# Core_CNC_shield.net
KiCad netlist of a schematic drawn in Altium Designer
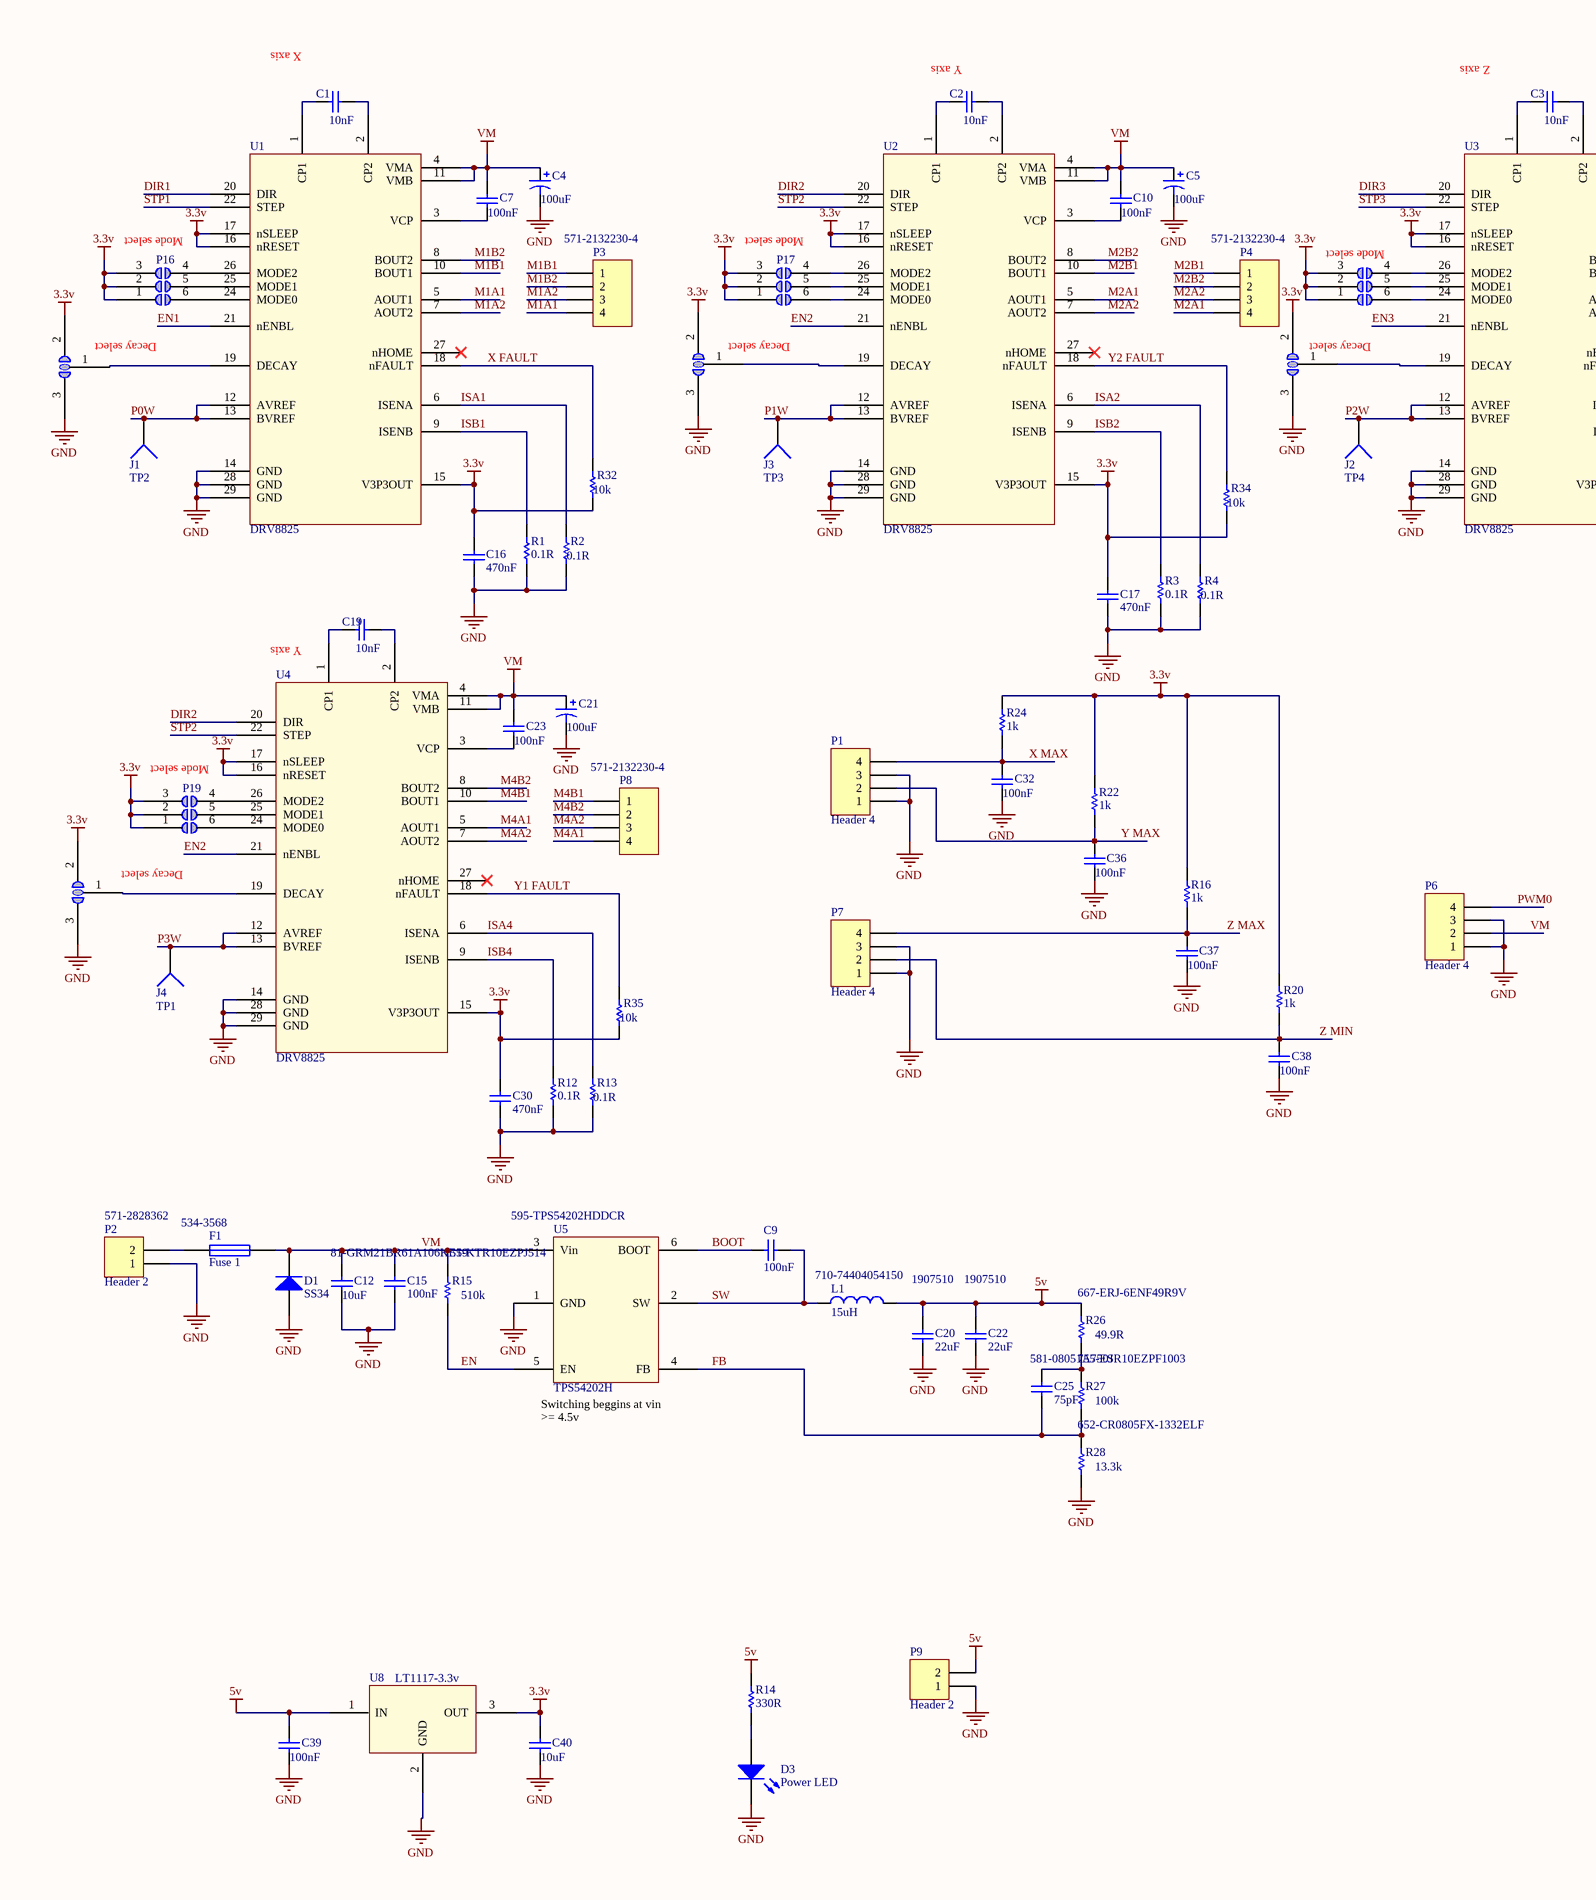
[diagram p0: Core CNC shield.SchDoc, left]
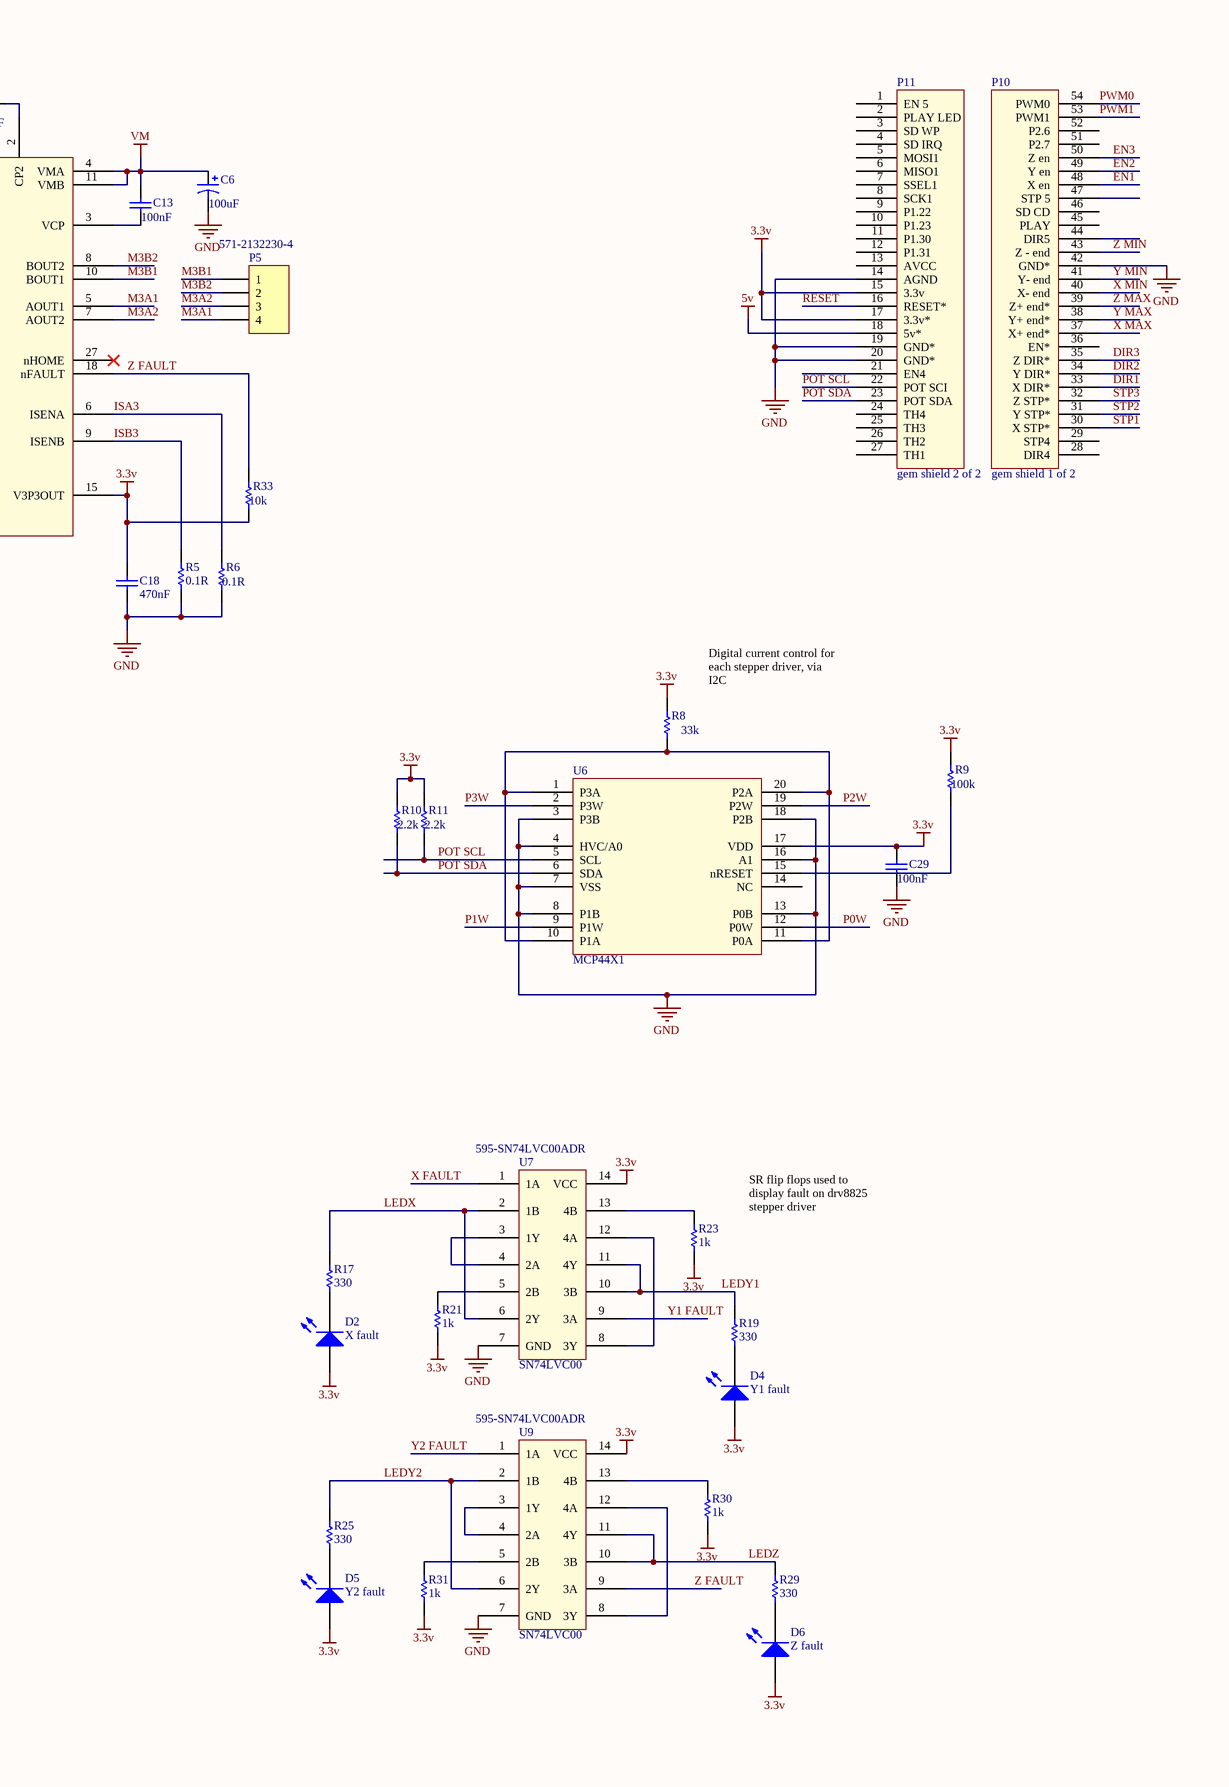
[diagram p1: Core CNC shield.SchDoc, right]

(export (version "E")
  (design (tool "Eeschema 10.0.6"))
  (components
    (comp (ref "C1")
      (value "10nF")
      (footprint "0805")
      (description "Capacitor")
      (fields (field (name "PUBLISHER") "Altium Limited"))
      (libsource (lib "Miscellaneous Devices") (part "Cap"))
    )
    (comp (ref "C2")
      (value "10nF")
      (footprint "0805")
      (description "Capacitor")
      (fields (field (name "PUBLISHER") "Altium Limited"))
      (libsource (lib "Miscellaneous Devices") (part "Cap"))
    )
    (comp (ref "C3")
      (value "10nF")
      (footprint "0805")
      (description "Capacitor")
      (fields (field (name "PUBLISHER") "Altium Limited"))
      (libsource (lib "Miscellaneous Devices") (part "Cap"))
    )
    (comp (ref "C4")
      (value "100uF")
      (footprint "470uf/ 100uf 50v smd")
      (description "Polarized Capacitor (Radial)")
      (fields (field (name "PUBLISHER") "Altium Limited"))
      (libsource (lib "Miscellaneous Devices") (part "Cap Pol1"))
    )
    (comp (ref "C5")
      (value "100uF")
      (footprint "470uf/ 100uf 50v smd")
      (description "Polarized Capacitor (Radial)")
      (fields (field (name "PUBLISHER") "Altium Limited"))
      (libsource (lib "Miscellaneous Devices") (part "Cap Pol1"))
    )
    (comp (ref "C6")
      (value "100uF")
      (footprint "470uf/ 100uf 50v smd")
      (description "Polarized Capacitor (Radial)")
      (fields (field (name "PUBLISHER") "Altium Limited"))
      (libsource (lib "Miscellaneous Devices") (part "Cap Pol1"))
    )
    (comp (ref "C7")
      (value "100nF")
      (footprint "0805")
      (description "Capacitor")
      (fields (field (name "PUBLISHER") "Altium Limited"))
      (libsource (lib "Miscellaneous Devices") (part "Cap"))
    )
    (comp (ref "C9")
      (value "100nF")
      (footprint "0805")
      (description "Capacitor")
      (fields (field (name "PUBLISHER") "Altium Limited"))
      (libsource (lib "Miscellaneous Devices") (part "Cap"))
    )
    (comp (ref "C10")
      (value "100nF")
      (footprint "0805")
      (description "Capacitor")
      (fields (field (name "PUBLISHER") "Altium Limited"))
      (libsource (lib "Miscellaneous Devices") (part "Cap"))
    )
    (comp (ref "C12")
      (value "10uF")
      (footprint "0805")
      (description "Capacitor")
      (fields
        (field (name "SUPPLIER PART NUMBER 1") "81-GRM21BR61A106KE19")
        (field (name "PUBLISHER") "Altium Limited")
      )
      (libsource (lib "Miscellaneous Devices") (part "Cap"))
    )
    (comp (ref "C13")
      (value "100nF")
      (footprint "0805")
      (description "Capacitor")
      (fields (field (name "PUBLISHER") "Altium Limited"))
      (libsource (lib "Miscellaneous Devices") (part "Cap"))
    )
    (comp (ref "C15")
      (value "100nF")
      (footprint "0805")
      (description "Capacitor")
      (fields (field (name "PUBLISHER") "Altium Limited"))
      (libsource (lib "Miscellaneous Devices") (part "Cap"))
    )
    (comp (ref "C16")
      (value "470nF")
      (footprint "0805")
      (description "Capacitor")
      (fields (field (name "PUBLISHER") "Altium Limited"))
      (libsource (lib "Miscellaneous Devices") (part "Cap"))
    )
    (comp (ref "C17")
      (value "470nF")
      (footprint "0805")
      (description "Capacitor")
      (fields (field (name "PUBLISHER") "Altium Limited"))
      (libsource (lib "Miscellaneous Devices") (part "Cap"))
    )
    (comp (ref "C18")
      (value "470nF")
      (footprint "0805")
      (description "Capacitor")
      (fields (field (name "PUBLISHER") "Altium Limited"))
      (libsource (lib "Miscellaneous Devices") (part "Cap"))
    )
    (comp (ref "C19")
      (value "10nF")
      (footprint "0805")
      (description "Capacitor")
      (fields (field (name "PUBLISHER") "Altium Limited"))
      (libsource (lib "Miscellaneous Devices") (part "Cap"))
    )
    (comp (ref "C20")
      (value "22uF")
      (footprint "0805")
      (description "Capacitor")
      (fields (field (name "SUPPLIER PART NUMBER 4") "1907510") (field (name "PUBLISHER") "Altium Limited"))
      (libsource (lib "Miscellaneous Devices") (part "Cap"))
    )
    (comp (ref "C21")
      (value "100uF")
      (footprint "470uf/ 100uf 50v smd")
      (description "Polarized Capacitor (Radial)")
      (fields (field (name "PUBLISHER") "Altium Limited"))
      (libsource (lib "Miscellaneous Devices") (part "Cap Pol1"))
    )
    (comp (ref "C22")
      (value "22uF")
      (footprint "0805")
      (description "Capacitor")
      (fields (field (name "SUPPLIER PART NUMBER 4") "1907510") (field (name "PUBLISHER") "Altium Limited"))
      (libsource (lib "Miscellaneous Devices") (part "Cap"))
    )
    (comp (ref "C23")
      (value "100nF")
      (footprint "0805")
      (description "Capacitor")
      (fields (field (name "PUBLISHER") "Altium Limited"))
      (libsource (lib "Miscellaneous Devices") (part "Cap"))
    )
    (comp (ref "C25")
      (value "75pF")
      (footprint "0805")
      (description "Capacitor")
      (fields
        (field (name "SUPPLIER PART NUMBER 1") "581-08051A750J")
        (field (name "PUBLISHER") "Altium Limited")
      )
      (libsource (lib "Miscellaneous Devices") (part "Cap"))
    )
    (comp (ref "C29")
      (value "100nF")
      (footprint "0805")
      (description "Capacitor")
      (fields (field (name "PUBLISHER") "Altium Limited"))
      (libsource (lib "Miscellaneous Devices") (part "Cap"))
    )
    (comp (ref "C30")
      (value "470nF")
      (footprint "0805")
      (description "Capacitor")
      (fields (field (name "PUBLISHER") "Altium Limited"))
      (libsource (lib "Miscellaneous Devices") (part "Cap"))
    )
    (comp (ref "C32")
      (value "100nF")
      (footprint "0805")
      (description "Capacitor")
      (fields (field (name "PUBLISHER") "Altium Limited"))
      (libsource (lib "Miscellaneous Devices") (part "Cap"))
    )
    (comp (ref "C36")
      (value "100nF")
      (footprint "0805")
      (description "Capacitor")
      (fields (field (name "PUBLISHER") "Altium Limited"))
      (libsource (lib "Miscellaneous Devices") (part "Cap"))
    )
    (comp (ref "C37")
      (value "100nF")
      (footprint "0805")
      (description "Capacitor")
      (fields (field (name "PUBLISHER") "Altium Limited"))
      (libsource (lib "Miscellaneous Devices") (part "Cap"))
    )
    (comp (ref "C38")
      (value "100nF")
      (footprint "0805")
      (description "Capacitor")
      (fields (field (name "PUBLISHER") "Altium Limited"))
      (libsource (lib "Miscellaneous Devices") (part "Cap"))
    )
    (comp (ref "C39")
      (value "100nF")
      (footprint "0805")
      (description "Capacitor")
      (fields (field (name "PUBLISHER") "Altium Limited"))
      (libsource (lib "Miscellaneous Devices") (part "Cap"))
    )
    (comp (ref "C40")
      (value "10uF")
      (footprint "0805")
      (description "Capacitor")
      (fields (field (name "PUBLISHER") "Altium Limited"))
      (libsource (lib "Miscellaneous Devices") (part "Cap"))
    )
    (comp (ref "D1")
      (value "SS34")
      (footprint "Diode")
      (description "Default Diode")
      (fields (field (name "PUBLISHER") "Altium Limited"))
      (libsource (lib "Miscellaneous Devices") (part "Diode"))
    )
    (comp (ref "D2")
      (value "X fault")
      (footprint "0805 LED")
      (description "Typical RED, GREEN, YELLOW, AMBER GaAs LED")
      (fields (field (name "PUBLISHER") "Altium Limited"))
      (libsource (lib "Miscellaneous Devices") (part "LED2"))
    )
    (comp (ref "D3")
      (value "Power LED")
      (footprint "0805 LED")
      (description "Typical RED, GREEN, YELLOW, AMBER GaAs LED")
      (fields (field (name "PUBLISHER") "Altium Limited"))
      (libsource (lib "Miscellaneous Devices") (part "LED2"))
    )
    (comp (ref "D4")
      (value "Y1 fault")
      (footprint "0805 LED")
      (description "Typical RED, GREEN, YELLOW, AMBER GaAs LED")
      (fields (field (name "PUBLISHER") "Altium Limited"))
      (libsource (lib "Miscellaneous Devices") (part "LED2"))
    )
    (comp (ref "D5")
      (value "Y2 fault")
      (footprint "0805 LED")
      (description "Typical RED, GREEN, YELLOW, AMBER GaAs LED")
      (fields (field (name "PUBLISHER") "Altium Limited"))
      (libsource (lib "Miscellaneous Devices") (part "LED2"))
    )
    (comp (ref "D6")
      (value "Z fault")
      (footprint "0805 LED")
      (description "Typical RED, GREEN, YELLOW, AMBER GaAs LED")
      (fields (field (name "PUBLISHER") "Altium Limited"))
      (libsource (lib "Miscellaneous Devices") (part "LED2"))
    )
    (comp (ref "F1")
      (value "Fuse 1")
      (footprint "mini auto fuse")
      (description "Fuse")
      (fields (field (name "SUPPLIER PART NUMBER 1") "534-3568") (field (name "PUBLISHER") "Altium Limited"))
      (libsource (lib "Miscellaneous Devices") (part "Fuse 1"))
    )
    (comp (ref "J1")
      (value "TP2")
      (footprint "test point")
      (description "Socket")
      (fields (field (name "PUBLISHER") "Altium Limited"))
      (libsource (lib "Miscellaneous Connectors") (part "Socket"))
    )
    (comp (ref "J2")
      (value "TP4")
      (footprint "test point")
      (description "Socket")
      (fields (field (name "PUBLISHER") "Altium Limited"))
      (libsource (lib "Miscellaneous Connectors") (part "Socket"))
    )
    (comp (ref "J3")
      (value "TP3")
      (footprint "test point")
      (description "Socket")
      (fields (field (name "PUBLISHER") "Altium Limited"))
      (libsource (lib "Miscellaneous Connectors") (part "Socket"))
    )
    (comp (ref "J4")
      (value "TP1")
      (footprint "test point")
      (description "Socket")
      (fields (field (name "PUBLISHER") "Altium Limited"))
      (libsource (lib "Miscellaneous Connectors") (part "Socket"))
    )
    (comp (ref "L1")
      (value "15uH")
      (footprint "SRN4018 inductor")
      (description "Inductor")
      (fields
        (field (name "SUPPLIER PART NUMBER 1") "710-74404054150")
        (field (name "Comment") "15uh")
        (field (name "PUBLISHER") "Altium Limited")
      )
      (libsource (lib "Miscellaneous Devices") (part "Inductor"))
    )
    (comp (ref "P1")
      (value "Header 4")
      (footprint "4 way screw")
      (description "Header, 4-Pin")
      (fields (field (name "PUBLISHER") "Altium Limited"))
      (libsource (lib "") (part "Header 4_1"))
    )
    (comp (ref "P2")
      (value "Header 2")
      (footprint "2 pin screw con")
      (description "Header, 2-Pin")
      (fields
        (field (name "SUPPLIER PART NUMBER 1") "571-2828362")
        (field (name "PUBLISHER") "Altium Limited")
      )
      (libsource (lib "Miscellaneous Connectors") (part "Header 2"))
    )
    (comp (ref "P3")
      (value "Header 4")
      (footprint "4 pin screw")
      (description "Header, 4-Pin")
      (fields
        (field (name "SUPPLIER PART NUMBER 1") "571-2132230-4")
        (field (name "PUBLISHER") "Altium Limited")
      )
      (libsource (lib "Miscellaneous Connectors") (part "Header 4"))
    )
    (comp (ref "P4")
      (value "Header 4")
      (footprint "4 pin screw")
      (description "Header, 4-Pin")
      (fields
        (field (name "SUPPLIER PART NUMBER 1") "571-2132230-4")
        (field (name "PUBLISHER") "Altium Limited")
      )
      (libsource (lib "Miscellaneous Connectors") (part "Header 4"))
    )
    (comp (ref "P5")
      (value "Header 4")
      (footprint "4 pin screw")
      (description "Header, 4-Pin")
      (fields
        (field (name "SUPPLIER PART NUMBER 1") "571-2132230-4")
        (field (name "PUBLISHER") "Altium Limited")
      )
      (libsource (lib "Miscellaneous Connectors") (part "Header 4"))
    )
    (comp (ref "P6")
      (value "Header 4")
      (footprint "4 way screw")
      (description "Header, 4-Pin")
      (fields (field (name "PUBLISHER") "Altium Limited"))
      (libsource (lib "") (part "Header 4_1"))
    )
    (comp (ref "P7")
      (value "Header 4")
      (footprint "4 way screw")
      (description "Header, 4-Pin")
      (fields (field (name "PUBLISHER") "Altium Limited"))
      (libsource (lib "") (part "Header 4_1"))
    )
    (comp (ref "P8")
      (value "Header 4")
      (footprint "4 pin screw")
      (description "Header, 4-Pin")
      (fields
        (field (name "SUPPLIER PART NUMBER 1") "571-2132230-4")
        (field (name "PUBLISHER") "Altium Limited")
      )
      (libsource (lib "Miscellaneous Connectors") (part "Header 4"))
    )
    (comp (ref "P9")
      (value "Header 2")
      (footprint "HDR1X2")
      (description "Header, 2-Pin")
      (fields (field (name "PUBLISHER") "Altium Limited"))
      (libsource (lib "Miscellaneous Connectors") (part "Header 2"))
    )
    (comp (ref "P10")
      (value "gem shield 1 of 2")
      (footprint "gem shield 1 of 2")
      (libsource (lib "32 bit cnc") (part "gem shield 1 of 2"))
    )
    (comp (ref "P11")
      (value "gem shield 2 of 2")
      (footprint "gem shield 2 of 2")
      (libsource (lib "32 bit cnc") (part "gem shield 2 of 2"))
    )
    (comp (ref "P14")
      (value "~")
      (footprint "2 way jumper")
      (libsource (lib "32 bit cnc") (part "voltage selector"))
    )
    (comp (ref "P15")
      (value "~")
      (footprint "2 way jumper")
      (libsource (lib "32 bit cnc") (part "voltage selector"))
    )
    (comp (ref "P16")
      (value "~")
      (footprint "3 way jumper")
      (libsource (lib "32 bit cnc") (part "3 way jumper"))
    )
    (comp (ref "P17")
      (value "~")
      (footprint "3 way jumper")
      (libsource (lib "32 bit cnc") (part "3 way jumper"))
    )
    (comp (ref "P18")
      (value "~")
      (footprint "3 way jumper")
      (libsource (lib "32 bit cnc") (part "3 way jumper"))
    )
    (comp (ref "P19")
      (value "~")
      (footprint "3 way jumper")
      (libsource (lib "32 bit cnc") (part "3 way jumper"))
    )
    (comp (ref "P20")
      (value "~")
      (footprint "2 way jumper")
      (libsource (lib "32 bit cnc") (part "voltage selector"))
    )
    (comp (ref "P21")
      (value "~")
      (footprint "2 way jumper")
      (libsource (lib "32 bit cnc") (part "voltage selector"))
    )
    (comp (ref "R1")
      (value "0.1R")
      (footprint "0805")
      (description "Resistor")
      (fields (field (name "PUBLISHER") "Altium Limited"))
      (libsource (lib "Miscellaneous Devices") (part "Res1"))
    )
    (comp (ref "R2")
      (value "0.1R")
      (footprint "0805")
      (description "Resistor")
      (fields (field (name "PUBLISHER") "Altium Limited"))
      (libsource (lib "Miscellaneous Devices") (part "Res1"))
    )
    (comp (ref "R3")
      (value "0.1R")
      (footprint "0805")
      (description "Resistor")
      (fields (field (name "PUBLISHER") "Altium Limited"))
      (libsource (lib "Miscellaneous Devices") (part "Res1"))
    )
    (comp (ref "R4")
      (value "0.1R")
      (footprint "0805")
      (description "Resistor")
      (fields (field (name "PUBLISHER") "Altium Limited"))
      (libsource (lib "Miscellaneous Devices") (part "Res1"))
    )
    (comp (ref "R5")
      (value "0.1R")
      (footprint "0805")
      (description "Resistor")
      (fields (field (name "PUBLISHER") "Altium Limited"))
      (libsource (lib "Miscellaneous Devices") (part "Res1"))
    )
    (comp (ref "R6")
      (value "0.1R")
      (footprint "0805")
      (description "Resistor")
      (fields (field (name "PUBLISHER") "Altium Limited"))
      (libsource (lib "Miscellaneous Devices") (part "Res1"))
    )
    (comp (ref "R8")
      (value "33k")
      (footprint "0805")
      (description "Resistor")
      (fields (field (name "PUBLISHER") "Altium Limited"))
      (libsource (lib "Miscellaneous Devices") (part "Res1"))
    )
    (comp (ref "R9")
      (value "100k")
      (footprint "0805")
      (description "Resistor")
      (fields (field (name "PUBLISHER") "Altium Limited"))
      (libsource (lib "Miscellaneous Devices") (part "Res1"))
    )
    (comp (ref "R10")
      (value "2.2k")
      (footprint "0805")
      (description "Resistor")
      (fields (field (name "PUBLISHER") "Altium Limited"))
      (libsource (lib "Miscellaneous Devices") (part "Res1"))
    )
    (comp (ref "R11")
      (value "2.2k")
      (footprint "0805")
      (description "Resistor")
      (fields (field (name "PUBLISHER") "Altium Limited"))
      (libsource (lib "Miscellaneous Devices") (part "Res1"))
    )
    (comp (ref "R12")
      (value "0.1R")
      (footprint "0805")
      (description "Resistor")
      (fields (field (name "PUBLISHER") "Altium Limited"))
      (libsource (lib "Miscellaneous Devices") (part "Res1"))
    )
    (comp (ref "R13")
      (value "0.1R")
      (footprint "0805")
      (description "Resistor")
      (fields (field (name "PUBLISHER") "Altium Limited"))
      (libsource (lib "Miscellaneous Devices") (part "Res1"))
    )
    (comp (ref "R14")
      (value "330R")
      (footprint "0805")
      (description "Resistor")
      (fields (field (name "PUBLISHER") "Altium Limited"))
      (libsource (lib "Miscellaneous Devices") (part "Res1"))
    )
    (comp (ref "R15")
      (value "510k")
      (footprint "0805")
      (description "Resistor")
      (fields
        (field (name "SUPPLIER PART NUMBER 1") "755-KTR10EZPJ514")
        (field (name "PUBLISHER") "Altium Limited")
      )
      (libsource (lib "Miscellaneous Devices") (part "Res1"))
    )
    (comp (ref "R16")
      (value "1k")
      (footprint "0805")
      (description "Resistor")
      (fields (field (name "PUBLISHER") "Altium Limited"))
      (libsource (lib "Miscellaneous Devices") (part "Res1"))
    )
    (comp (ref "R17")
      (value "330")
      (footprint "0805")
      (description "Resistor")
      (fields (field (name "Comment") "330R") (field (name "PUBLISHER") "Altium Limited"))
      (libsource (lib "Miscellaneous Devices") (part "Res1"))
    )
    (comp (ref "R19")
      (value "330")
      (footprint "0805")
      (description "Resistor")
      (fields (field (name "Comment") "330R") (field (name "PUBLISHER") "Altium Limited"))
      (libsource (lib "Miscellaneous Devices") (part "Res1"))
    )
    (comp (ref "R20")
      (value "1k")
      (footprint "0805")
      (description "Resistor")
      (fields (field (name "PUBLISHER") "Altium Limited"))
      (libsource (lib "Miscellaneous Devices") (part "Res1"))
    )
    (comp (ref "R21")
      (value "1k")
      (footprint "0805")
      (description "Resistor")
      (fields (field (name "PUBLISHER") "Altium Limited"))
      (libsource (lib "Miscellaneous Devices") (part "Res1"))
    )
    (comp (ref "R22")
      (value "1k")
      (footprint "0805")
      (description "Resistor")
      (fields (field (name "PUBLISHER") "Altium Limited"))
      (libsource (lib "Miscellaneous Devices") (part "Res1"))
    )
    (comp (ref "R23")
      (value "1k")
      (footprint "0805")
      (description "Resistor")
      (fields (field (name "PUBLISHER") "Altium Limited"))
      (libsource (lib "Miscellaneous Devices") (part "Res1"))
    )
    (comp (ref "R24")
      (value "1k")
      (footprint "0805")
      (description "Resistor")
      (fields (field (name "PUBLISHER") "Altium Limited"))
      (libsource (lib "Miscellaneous Devices") (part "Res1"))
    )
    (comp (ref "R25")
      (value "330")
      (footprint "0805")
      (description "Resistor")
      (fields (field (name "Comment") "330R") (field (name "PUBLISHER") "Altium Limited"))
      (libsource (lib "Miscellaneous Devices") (part "Res1"))
    )
    (comp (ref "R26")
      (value "49.9R")
      (footprint "0805")
      (description "Resistor")
      (fields
        (field (name "SUPPLIER PART NUMBER 1") "667-ERJ-6ENF49R9V")
        (field (name "PUBLISHER") "Altium Limited")
      )
      (libsource (lib "Miscellaneous Devices") (part "Res1"))
    )
    (comp (ref "R27")
      (value "100k")
      (footprint "0805")
      (description "Resistor")
      (fields
        (field (name "SUPPLIER PART NUMBER 1") "755-ESR10EZPF1003")
        (field (name "PUBLISHER") "Altium Limited")
      )
      (libsource (lib "Miscellaneous Devices") (part "Res1"))
    )
    (comp (ref "R28")
      (value "13.3k")
      (footprint "0805")
      (description "Resistor")
      (fields
        (field (name "SUPPLIER PART NUMBER 1") "652-CR0805FX-1332ELF")
        (field (name "PUBLISHER") "Altium Limited")
      )
      (libsource (lib "Miscellaneous Devices") (part "Res1"))
    )
    (comp (ref "R29")
      (value "330")
      (footprint "0805")
      (description "Resistor")
      (fields (field (name "Comment") "330R") (field (name "PUBLISHER") "Altium Limited"))
      (libsource (lib "Miscellaneous Devices") (part "Res1"))
    )
    (comp (ref "R30")
      (value "1k")
      (footprint "0805")
      (description "Resistor")
      (fields (field (name "PUBLISHER") "Altium Limited"))
      (libsource (lib "Miscellaneous Devices") (part "Res1"))
    )
    (comp (ref "R31")
      (value "1k")
      (footprint "0805")
      (description "Resistor")
      (fields (field (name "PUBLISHER") "Altium Limited"))
      (libsource (lib "Miscellaneous Devices") (part "Res1"))
    )
    (comp (ref "R32")
      (value "10k")
      (footprint "0805")
      (description "Resistor")
      (fields (field (name "Comment") "0.1R") (field (name "PUBLISHER") "Altium Limited"))
      (libsource (lib "Miscellaneous Devices") (part "Res1"))
    )
    (comp (ref "R33")
      (value "10k")
      (footprint "0805")
      (description "Resistor")
      (fields (field (name "Comment") "0.1R") (field (name "PUBLISHER") "Altium Limited"))
      (libsource (lib "Miscellaneous Devices") (part "Res1"))
    )
    (comp (ref "R34")
      (value "10k")
      (footprint "0805")
      (description "Resistor")
      (fields (field (name "Comment") "0.1R") (field (name "PUBLISHER") "Altium Limited"))
      (libsource (lib "Miscellaneous Devices") (part "Res1"))
    )
    (comp (ref "R35")
      (value "10k")
      (footprint "0805")
      (description "Resistor")
      (fields (field (name "Comment") "0.1R") (field (name "PUBLISHER") "Altium Limited"))
      (libsource (lib "Miscellaneous Devices") (part "Res1"))
    )
    (comp (ref "U1")
      (value "DRV8825")
      (footprint "DRV8825 ic")
      (libsource (lib "32 bit cnc") (part "DRV8825 ic"))
    )
    (comp (ref "U2")
      (value "DRV8825")
      (footprint "DRV8825 ic")
      (libsource (lib "32 bit cnc") (part "DRV8825 ic"))
    )
    (comp (ref "U3")
      (value "DRV8825")
      (footprint "DRV8825 ic")
      (libsource (lib "32 bit cnc") (part "DRV8825 ic"))
    )
    (comp (ref "U4")
      (value "DRV8825")
      (footprint "DRV8825 ic")
      (libsource (lib "32 bit cnc") (part "DRV8825 ic"))
    )
    (comp (ref "U5")
      (value "TPS54202H")
      (footprint "TPS54202H")
      (fields (field (name "SUPPLIER PART NUMBER 1") "595-TPS54202HDDCR"))
      (libsource (lib "32 bit cnc") (part "TPS5420H"))
    )
    (comp (ref "U6") (value "MCP44X1") (footprint "MCP44X1") (libsource (lib "32 bit cnc") (part "MCP44X1")))
    (comp (ref "U7")
      (value "SN74LVC00")
      (footprint "sn74lv00")
      (fields (field (name "SUPPLIER PART NUMBER 1") "595-SN74LVC00ADR"))
      (libsource (lib "32 bit cnc") (part "SN74LVC00"))
    )
    (comp (ref "U8")
      (value "LT1117-3.3v")
      (footprint "SOT223")
      (libsource (lib "32 bit cnc") (part "LT1117-3.3v"))
    )
    (comp (ref "U9")
      (value "SN74LVC00")
      (footprint "sn74lv00")
      (fields (field (name "SUPPLIER PART NUMBER 1") "595-SN74LVC00ADR"))
      (libsource (lib "32 bit cnc") (part "SN74LVC00"))
    )
  )
  (nets
    (net (code "1") (name "/BOOT") (class "Default")
      (node (ref "C9") (pin "2") (pinfunction "2_2") (pintype "passive"))
      (node (ref "U5") (pin "6") (pinfunction "BOOT_6") (pintype "passive"))
    )
    (net (code "2") (name "/DIR1") (class "Default")
      (node (ref "P10") (pin "33") (pinfunction "X_DIR*_33") (pintype "passive"))
      (node (ref "U1") (pin "20") (pinfunction "DIR_20") (pintype "passive"))
    )
    (net (code "3") (name "/DIR2") (class "Default")
      (node (ref "P10") (pin "34") (pinfunction "Y_DIR*_34") (pintype "passive"))
      (node (ref "U2") (pin "20") (pinfunction "DIR_20") (pintype "passive"))
      (node (ref "U4") (pin "20") (pinfunction "DIR_20") (pintype "passive"))
    )
    (net (code "4") (name "/DIR3") (class "Default")
      (node (ref "P10") (pin "35") (pinfunction "Z_DIR*_35") (pintype "passive"))
      (node (ref "U3") (pin "20") (pinfunction "DIR_20") (pintype "passive"))
    )
    (net (code "5") (name "/EN") (class "Default")
      (node (ref "R15") (pin "1") (pinfunction "1_1") (pintype "passive"))
      (node (ref "U5") (pin "5") (pinfunction "EN_5") (pintype "passive"))
    )
    (net (code "6") (name "/EN1") (class "Default")
      (node (ref "P10") (pin "48") (pinfunction "X_en_48") (pintype "passive"))
      (node (ref "U1") (pin "21") (pinfunction "nENBL_21") (pintype "passive"))
    )
    (net (code "7") (name "/EN2") (class "Default")
      (node (ref "P10") (pin "49") (pinfunction "Y_en_49") (pintype "passive"))
      (node (ref "U2") (pin "21") (pinfunction "nENBL_21") (pintype "passive"))
      (node (ref "U4") (pin "21") (pinfunction "nENBL_21") (pintype "passive"))
    )
    (net (code "8") (name "/EN3") (class "Default")
      (node (ref "P10") (pin "50") (pinfunction "Z_en_50") (pintype "passive"))
      (node (ref "U3") (pin "21") (pinfunction "nENBL_21") (pintype "passive"))
    )
    (net (code "9") (name "/FB") (class "Default")
      (node (ref "C25") (pin "2") (pinfunction "2_2") (pintype "passive"))
      (node (ref "R27") (pin "1") (pinfunction "1_1") (pintype "passive"))
      (node (ref "R28") (pin "2") (pinfunction "2_2") (pintype "passive"))
      (node (ref "U5") (pin "4") (pinfunction "FB_4") (pintype "passive"))
    )
    (net (code "10") (name "/ISA1") (class "Default")
      (node (ref "R2") (pin "2") (pinfunction "2_2") (pintype "passive"))
      (node (ref "U1") (pin "6") (pinfunction "ISENA_6") (pintype "passive"))
    )
    (net (code "11") (name "/ISA2") (class "Default")
      (node (ref "R4") (pin "2") (pinfunction "2_2") (pintype "passive"))
      (node (ref "U2") (pin "6") (pinfunction "ISENA_6") (pintype "passive"))
    )
    (net (code "12") (name "/ISA3") (class "Default")
      (node (ref "R6") (pin "2") (pinfunction "2_2") (pintype "passive"))
      (node (ref "U3") (pin "6") (pinfunction "ISENA_6") (pintype "passive"))
    )
    (net (code "13") (name "/ISA4") (class "Default")
      (node (ref "R13") (pin "2") (pinfunction "2_2") (pintype "passive"))
      (node (ref "U4") (pin "6") (pinfunction "ISENA_6") (pintype "passive"))
    )
    (net (code "14") (name "/ISB1") (class "Default")
      (node (ref "R1") (pin "1") (pinfunction "1_1") (pintype "passive"))
      (node (ref "U1") (pin "9") (pinfunction "ISENB_9") (pintype "passive"))
    )
    (net (code "15") (name "/ISB2") (class "Default")
      (node (ref "R3") (pin "1") (pinfunction "1_1") (pintype "passive"))
      (node (ref "U2") (pin "9") (pinfunction "ISENB_9") (pintype "passive"))
    )
    (net (code "16") (name "/ISB3") (class "Default")
      (node (ref "R5") (pin "1") (pinfunction "1_1") (pintype "passive"))
      (node (ref "U3") (pin "9") (pinfunction "ISENB_9") (pintype "passive"))
    )
    (net (code "17") (name "/ISB4") (class "Default")
      (node (ref "R12") (pin "1") (pinfunction "1_1") (pintype "passive"))
      (node (ref "U4") (pin "9") (pinfunction "ISENB_9") (pintype "passive"))
    )
    (net (code "18") (name "/LEDX") (class "Default")
      (node (ref "R17") (pin "1") (pinfunction "1_1") (pintype "passive"))
      (node (ref "U7") (pin "2") (pinfunction "1B_2") (pintype "passive"))
      (node (ref "U7") (pin "6") (pinfunction "2Y_6") (pintype "passive"))
    )
    (net (code "19") (name "/LEDY1") (class "Default")
      (node (ref "R19") (pin "1") (pinfunction "1_1") (pintype "passive"))
      (node (ref "U7") (pin "10") (pinfunction "3B_10") (pintype "passive"))
      (node (ref "U7") (pin "11") (pinfunction "4Y_11") (pintype "passive"))
    )
    (net (code "20") (name "/LEDY2") (class "Default")
      (node (ref "R25") (pin "1") (pinfunction "1_1") (pintype "passive"))
      (node (ref "U9") (pin "2") (pinfunction "1B_2") (pintype "passive"))
      (node (ref "U9") (pin "6") (pinfunction "2Y_6") (pintype "passive"))
    )
    (net (code "21") (name "/LEDZ") (class "Default")
      (node (ref "R29") (pin "1") (pinfunction "1_1") (pintype "passive"))
      (node (ref "U9") (pin "10") (pinfunction "3B_10") (pintype "passive"))
      (node (ref "U9") (pin "11") (pinfunction "4Y_11") (pintype "passive"))
    )
    (net (code "22") (name "/M1A1") (class "Default")
      (node (ref "P3") (pin "4") (pinfunction "4_4") (pintype "passive"))
      (node (ref "U1") (pin "5") (pinfunction "AOUT1_5") (pintype "passive"))
    )
    (net (code "23") (name "/M1A2") (class "Default")
      (node (ref "P3") (pin "3") (pinfunction "3_3") (pintype "passive"))
      (node (ref "U1") (pin "7") (pinfunction "AOUT2_7") (pintype "passive"))
    )
    (net (code "24") (name "/M1B1") (class "Default")
      (node (ref "P3") (pin "1") (pinfunction "1_1") (pintype "passive"))
      (node (ref "U1") (pin "10") (pinfunction "BOUT1_10") (pintype "passive"))
    )
    (net (code "25") (name "/M1B2") (class "Default")
      (node (ref "P3") (pin "2") (pinfunction "2_2") (pintype "passive"))
      (node (ref "U1") (pin "8") (pinfunction "BOUT2_8") (pintype "passive"))
    )
    (net (code "26") (name "/M2A1") (class "Default")
      (node (ref "P4") (pin "4") (pinfunction "4_4") (pintype "passive"))
      (node (ref "U2") (pin "5") (pinfunction "AOUT1_5") (pintype "passive"))
    )
    (net (code "27") (name "/M2A2") (class "Default")
      (node (ref "P4") (pin "3") (pinfunction "3_3") (pintype "passive"))
      (node (ref "U2") (pin "7") (pinfunction "AOUT2_7") (pintype "passive"))
    )
    (net (code "28") (name "/M2B1") (class "Default")
      (node (ref "P4") (pin "1") (pinfunction "1_1") (pintype "passive"))
      (node (ref "U2") (pin "10") (pinfunction "BOUT1_10") (pintype "passive"))
    )
    (net (code "29") (name "/M2B2") (class "Default")
      (node (ref "P4") (pin "2") (pinfunction "2_2") (pintype "passive"))
      (node (ref "U2") (pin "8") (pinfunction "BOUT2_8") (pintype "passive"))
    )
    (net (code "30") (name "/M3A1") (class "Default")
      (node (ref "P5") (pin "4") (pinfunction "4_4") (pintype "passive"))
      (node (ref "U3") (pin "5") (pinfunction "AOUT1_5") (pintype "passive"))
    )
    (net (code "31") (name "/M3A2") (class "Default")
      (node (ref "P5") (pin "3") (pinfunction "3_3") (pintype "passive"))
      (node (ref "U3") (pin "7") (pinfunction "AOUT2_7") (pintype "passive"))
    )
    (net (code "32") (name "/M3B1") (class "Default")
      (node (ref "P5") (pin "1") (pinfunction "1_1") (pintype "passive"))
      (node (ref "U3") (pin "10") (pinfunction "BOUT1_10") (pintype "passive"))
    )
    (net (code "33") (name "/M3B2") (class "Default")
      (node (ref "P5") (pin "2") (pinfunction "2_2") (pintype "passive"))
      (node (ref "U3") (pin "8") (pinfunction "BOUT2_8") (pintype "passive"))
    )
    (net (code "34") (name "/M4A1") (class "Default")
      (node (ref "P8") (pin "4") (pinfunction "4_4") (pintype "passive"))
      (node (ref "U4") (pin "5") (pinfunction "AOUT1_5") (pintype "passive"))
    )
    (net (code "35") (name "/M4A2") (class "Default")
      (node (ref "P8") (pin "3") (pinfunction "3_3") (pintype "passive"))
      (node (ref "U4") (pin "7") (pinfunction "AOUT2_7") (pintype "passive"))
    )
    (net (code "36") (name "/M4B1") (class "Default")
      (node (ref "P8") (pin "1") (pinfunction "1_1") (pintype "passive"))
      (node (ref "U4") (pin "10") (pinfunction "BOUT1_10") (pintype "passive"))
    )
    (net (code "37") (name "/M4B2") (class "Default")
      (node (ref "P8") (pin "2") (pinfunction "2_2") (pintype "passive"))
      (node (ref "U4") (pin "8") (pinfunction "BOUT2_8") (pintype "passive"))
    )
    (net (code "38") (name "/P0W") (class "Default")
      (node (ref "J1") (pin "1") (pinfunction "1_1") (pintype "passive"))
      (node (ref "U1") (pin "12") (pinfunction "AVREF_12") (pintype "passive"))
      (node (ref "U1") (pin "13") (pinfunction "BVREF_13") (pintype "passive"))
      (node (ref "U6") (pin "12") (pinfunction "P0W_12") (pintype "passive"))
    )
    (net (code "39") (name "/P1W") (class "Default")
      (node (ref "J3") (pin "1") (pinfunction "1_1") (pintype "passive"))
      (node (ref "U2") (pin "12") (pinfunction "AVREF_12") (pintype "passive"))
      (node (ref "U2") (pin "13") (pinfunction "BVREF_13") (pintype "passive"))
      (node (ref "U6") (pin "9") (pinfunction "P1W_9") (pintype "passive"))
    )
    (net (code "40") (name "/P2W") (class "Default")
      (node (ref "J2") (pin "1") (pinfunction "1_1") (pintype "passive"))
      (node (ref "U3") (pin "12") (pinfunction "AVREF_12") (pintype "passive"))
      (node (ref "U3") (pin "13") (pinfunction "BVREF_13") (pintype "passive"))
      (node (ref "U6") (pin "19") (pinfunction "P2W_19") (pintype "passive"))
    )
    (net (code "41") (name "/P3W") (class "Default")
      (node (ref "J4") (pin "1") (pinfunction "1_1") (pintype "passive"))
      (node (ref "U4") (pin "12") (pinfunction "AVREF_12") (pintype "passive"))
      (node (ref "U4") (pin "13") (pinfunction "BVREF_13") (pintype "passive"))
      (node (ref "U6") (pin "2") (pinfunction "P3W_2") (pintype "passive"))
    )
    (net (code "42") (name "/POT SCL") (class "Default")
      (node (ref "P11") (pin "22") (pinfunction "POT_SCI_22") (pintype "passive"))
      (node (ref "R11") (pin "1") (pinfunction "1_1") (pintype "passive"))
      (node (ref "U6") (pin "5") (pinfunction "SCL_5") (pintype "passive"))
    )
    (net (code "43") (name "/POT SDA") (class "Default")
      (node (ref "P11") (pin "23") (pinfunction "POT_SDA_23") (pintype "passive"))
      (node (ref "R10") (pin "1") (pinfunction "1_1") (pintype "passive"))
      (node (ref "U6") (pin "6") (pinfunction "SDA_6") (pintype "passive"))
    )
    (net (code "44") (name "/PWM0") (class "Default")
      (node (ref "P10") (pin "54") (pinfunction "PWM0_54") (pintype "passive"))
      (node (ref "P6") (pin "4") (pinfunction "4_4") (pintype "passive"))
    )
    (net (code "45") (name "/PWM1") (class "Default")
      (node (ref "P10") (pin "53") (pinfunction "PWM1_53") (pintype "passive"))
    )
    (net (code "46") (name "/RESET") (class "Default")
      (node (ref "P11") (pin "16") (pinfunction "RESET*_16") (pintype "passive"))
    )
    (net (code "47") (name "/STP1") (class "Default")
      (node (ref "P10") (pin "30") (pinfunction "X_STP*_30") (pintype "passive"))
      (node (ref "U1") (pin "22") (pinfunction "STEP_22") (pintype "passive"))
    )
    (net (code "48") (name "/STP2") (class "Default")
      (node (ref "P10") (pin "31") (pinfunction "Y_STP*_31") (pintype "passive"))
      (node (ref "U2") (pin "22") (pinfunction "STEP_22") (pintype "passive"))
      (node (ref "U4") (pin "22") (pinfunction "STEP_22") (pintype "passive"))
    )
    (net (code "49") (name "/STP3") (class "Default")
      (node (ref "P10") (pin "32") (pinfunction "Z_STP*_32") (pintype "passive"))
      (node (ref "U3") (pin "22") (pinfunction "STEP_22") (pintype "passive"))
    )
    (net (code "50") (name "/SW") (class "Default")
      (node (ref "C9") (pin "1") (pinfunction "1_1") (pintype "passive"))
      (node (ref "L1") (pin "1") (pinfunction "1_1") (pintype "passive"))
      (node (ref "U5") (pin "2") (pinfunction "SW_2") (pintype "passive"))
    )
    (net (code "51") (name "/X FAULT") (class "Default")
      (node (ref "R32") (pin "2") (pinfunction "2_2") (pintype "passive"))
      (node (ref "U1") (pin "18") (pinfunction "nFAULT_18") (pintype "passive"))
      (node (ref "U7") (pin "1") (pinfunction "1A_1") (pintype "passive"))
    )
    (net (code "52") (name "/X MAX") (class "Default")
      (node (ref "C32") (pin "2") (pinfunction "2_2") (pintype "passive"))
      (node (ref "P1") (pin "4") (pinfunction "4_4") (pintype "passive"))
      (node (ref "P10") (pin "37") (pinfunction "X+_end*_37") (pintype "passive"))
      (node (ref "R24") (pin "2") (pinfunction "2_2") (pintype "passive"))
    )
    (net (code "53") (name "/X MIN") (class "Default")
      (node (ref "P10") (pin "40") (pinfunction "X-_end_40") (pintype "passive"))
    )
    (net (code "54") (name "/Y MAX") (class "Default")
      (node (ref "C36") (pin "2") (pinfunction "2_2") (pintype "passive"))
      (node (ref "P1") (pin "2") (pinfunction "2_2") (pintype "passive"))
      (node (ref "P10") (pin "38") (pinfunction "Y+_end*_38") (pintype "passive"))
      (node (ref "R22") (pin "2") (pinfunction "2_2") (pintype "passive"))
    )
    (net (code "55") (name "/Y MIN") (class "Default")
      (node (ref "P10") (pin "41") (pinfunction "Y-_end_41") (pintype "passive"))
    )
    (net (code "56") (name "/Y1 FAULT") (class "Default")
      (node (ref "R35") (pin "2") (pinfunction "2_2") (pintype "passive"))
      (node (ref "U4") (pin "18") (pinfunction "nFAULT_18") (pintype "passive"))
      (node (ref "U7") (pin "9") (pinfunction "3A_9") (pintype "passive"))
    )
    (net (code "57") (name "/Y2 FAULT") (class "Default")
      (node (ref "R34") (pin "2") (pinfunction "2_2") (pintype "passive"))
      (node (ref "U2") (pin "18") (pinfunction "nFAULT_18") (pintype "passive"))
      (node (ref "U9") (pin "1") (pinfunction "1A_1") (pintype "passive"))
    )
    (net (code "58") (name "/Z FAULT") (class "Default")
      (node (ref "R33") (pin "2") (pinfunction "2_2") (pintype "passive"))
      (node (ref "U3") (pin "18") (pinfunction "nFAULT_18") (pintype "passive"))
      (node (ref "U9") (pin "9") (pinfunction "3A_9") (pintype "passive"))
    )
    (net (code "59") (name "/Z MAX") (class "Default")
      (node (ref "C37") (pin "2") (pinfunction "2_2") (pintype "passive"))
      (node (ref "P10") (pin "39") (pinfunction "Z+_end*_39") (pintype "passive"))
      (node (ref "P7") (pin "4") (pinfunction "4_4") (pintype "passive"))
      (node (ref "R16") (pin "2") (pinfunction "2_2") (pintype "passive"))
    )
    (net (code "60") (name "/Z MIN") (class "Default")
      (node (ref "C38") (pin "2") (pinfunction "2_2") (pintype "passive"))
      (node (ref "P10") (pin "43") (pinfunction "Z_-_end_43") (pintype "passive"))
      (node (ref "P7") (pin "2") (pinfunction "2_2") (pintype "passive"))
      (node (ref "R20") (pin "2") (pinfunction "2_2") (pintype "passive"))
    )
    (net (code "61") (name "3.3v") (class "Default")
      (node (ref "C16") (pin "2") (pinfunction "2_2") (pintype "passive"))
      (node (ref "C17") (pin "2") (pinfunction "2_2") (pintype "passive"))
      (node (ref "C18") (pin "2") (pinfunction "2_2") (pintype "passive"))
      (node (ref "C29") (pin "2") (pinfunction "2_2") (pintype "passive"))
      (node (ref "C30") (pin "2") (pinfunction "2_2") (pintype "passive"))
      (node (ref "C40") (pin "2") (pinfunction "2_2") (pintype "passive"))
      (node (ref "D2") (pin "1") (pinfunction "A_1") (pintype "passive"))
      (node (ref "D4") (pin "1") (pinfunction "A_1") (pintype "passive"))
      (node (ref "D5") (pin "1") (pinfunction "A_1") (pintype "passive"))
      (node (ref "D6") (pin "1") (pinfunction "A_1") (pintype "passive"))
      (node (ref "P11") (pin "15") (pinfunction "3.3v_15") (pintype "passive"))
      (node (ref "P11") (pin "17") (pinfunction "3.3v*_17") (pintype "passive"))
      (node (ref "P14") (pin "2") (pinfunction "2_2") (pintype "passive"))
      (node (ref "P15") (pin "2") (pinfunction "2_2") (pintype "passive"))
      (node (ref "P16") (pin "1") (pinfunction "17_1") (pintype "passive"))
      (node (ref "P16") (pin "2") (pinfunction "2_2") (pintype "passive"))
      (node (ref "P16") (pin "3") (pinfunction "3_3") (pintype "passive"))
      (node (ref "P17") (pin "1") (pinfunction "17_1") (pintype "passive"))
      (node (ref "P17") (pin "2") (pinfunction "2_2") (pintype "passive"))
      (node (ref "P17") (pin "3") (pinfunction "3_3") (pintype "passive"))
      (node (ref "P18") (pin "1") (pinfunction "17_1") (pintype "passive"))
      (node (ref "P18") (pin "2") (pinfunction "2_2") (pintype "passive"))
      (node (ref "P18") (pin "3") (pinfunction "3_3") (pintype "passive"))
      (node (ref "P19") (pin "1") (pinfunction "17_1") (pintype "passive"))
      (node (ref "P19") (pin "2") (pinfunction "2_2") (pintype "passive"))
      (node (ref "P19") (pin "3") (pinfunction "3_3") (pintype "passive"))
      (node (ref "P20") (pin "2") (pinfunction "2_2") (pintype "passive"))
      (node (ref "P21") (pin "2") (pinfunction "2_2") (pintype "passive"))
      (node (ref "R10") (pin "2") (pinfunction "2_2") (pintype "passive"))
      (node (ref "R11") (pin "2") (pinfunction "2_2") (pintype "passive"))
      (node (ref "R16") (pin "1") (pinfunction "1_1") (pintype "passive"))
      (node (ref "R20") (pin "1") (pinfunction "1_1") (pintype "passive"))
      (node (ref "R21") (pin "2") (pinfunction "2_2") (pintype "passive"))
      (node (ref "R22") (pin "1") (pinfunction "1_1") (pintype "passive"))
      (node (ref "R23") (pin "2") (pinfunction "2_2") (pintype "passive"))
      (node (ref "R24") (pin "1") (pinfunction "1_1") (pintype "passive"))
      (node (ref "R30") (pin "2") (pinfunction "2_2") (pintype "passive"))
      (node (ref "R31") (pin "2") (pinfunction "2_2") (pintype "passive"))
      (node (ref "R32") (pin "1") (pinfunction "1_1") (pintype "passive"))
      (node (ref "R33") (pin "1") (pinfunction "1_1") (pintype "passive"))
      (node (ref "R34") (pin "1") (pinfunction "1_1") (pintype "passive"))
      (node (ref "R35") (pin "1") (pinfunction "1_1") (pintype "passive"))
      (node (ref "R8") (pin "2") (pinfunction "2_2") (pintype "passive"))
      (node (ref "R9") (pin "2") (pinfunction "2_2") (pintype "passive"))
      (node (ref "U1") (pin "15") (pinfunction "V3P3OUT_15") (pintype "passive"))
      (node (ref "U1") (pin "16") (pinfunction "nRESET_16") (pintype "passive"))
      (node (ref "U1") (pin "17") (pinfunction "nSLEEP_17") (pintype "passive"))
      (node (ref "U2") (pin "15") (pinfunction "V3P3OUT_15") (pintype "passive"))
      (node (ref "U2") (pin "16") (pinfunction "nRESET_16") (pintype "passive"))
      (node (ref "U2") (pin "17") (pinfunction "nSLEEP_17") (pintype "passive"))
      (node (ref "U3") (pin "15") (pinfunction "V3P3OUT_15") (pintype "passive"))
      (node (ref "U3") (pin "16") (pinfunction "nRESET_16") (pintype "passive"))
      (node (ref "U3") (pin "17") (pinfunction "nSLEEP_17") (pintype "passive"))
      (node (ref "U4") (pin "15") (pinfunction "V3P3OUT_15") (pintype "passive"))
      (node (ref "U4") (pin "16") (pinfunction "nRESET_16") (pintype "passive"))
      (node (ref "U4") (pin "17") (pinfunction "nSLEEP_17") (pintype "passive"))
      (node (ref "U6") (pin "17") (pinfunction "VDD_17") (pintype "passive"))
      (node (ref "U7") (pin "14") (pinfunction "VCC_14") (pintype "passive"))
      (node (ref "U8") (pin "3") (pinfunction "OUT_3") (pintype "passive"))
      (node (ref "U9") (pin "14") (pinfunction "VCC_14") (pintype "passive"))
    )
    (net (code "62") (name "5v") (class "Default")
      (node (ref "C20") (pin "1") (pinfunction "1_1") (pintype "passive"))
      (node (ref "C22") (pin "1") (pinfunction "1_1") (pintype "passive"))
      (node (ref "C39") (pin "2") (pinfunction "2_2") (pintype "passive"))
      (node (ref "L1") (pin "2") (pinfunction "2_2") (pintype "passive"))
      (node (ref "P11") (pin "18") (pinfunction "5v*_18") (pintype "passive"))
      (node (ref "P9") (pin "2") (pinfunction "2_2") (pintype "passive"))
      (node (ref "R14") (pin "1") (pinfunction "1_1") (pintype "passive"))
      (node (ref "R26") (pin "2") (pinfunction "2_2") (pintype "passive"))
      (node (ref "U8") (pin "1") (pinfunction "IN_1") (pintype "passive"))
    )
    (net (code "63") (name "GND") (class "Default")
      (node (ref "C12") (pin "1") (pinfunction "1_1") (pintype "passive"))
      (node (ref "C15") (pin "2") (pinfunction "2_2") (pintype "passive"))
      (node (ref "C16") (pin "1") (pinfunction "1_1") (pintype "passive"))
      (node (ref "C17") (pin "1") (pinfunction "1_1") (pintype "passive"))
      (node (ref "C18") (pin "1") (pinfunction "1_1") (pintype "passive"))
      (node (ref "C20") (pin "2") (pinfunction "2_2") (pintype "passive"))
      (node (ref "C21") (pin "2") (pinfunction "2_2") (pintype "passive"))
      (node (ref "C22") (pin "2") (pinfunction "2_2") (pintype "passive"))
      (node (ref "C29") (pin "1") (pinfunction "1_1") (pintype "passive"))
      (node (ref "C30") (pin "1") (pinfunction "1_1") (pintype "passive"))
      (node (ref "C32") (pin "1") (pinfunction "1_1") (pintype "passive"))
      (node (ref "C36") (pin "1") (pinfunction "1_1") (pintype "passive"))
      (node (ref "C37") (pin "1") (pinfunction "1_1") (pintype "passive"))
      (node (ref "C38") (pin "1") (pinfunction "1_1") (pintype "passive"))
      (node (ref "C39") (pin "1") (pinfunction "1_1") (pintype "passive"))
      (node (ref "C4") (pin "2") (pinfunction "2_2") (pintype "passive"))
      (node (ref "C40") (pin "1") (pinfunction "1_1") (pintype "passive"))
      (node (ref "C5") (pin "2") (pinfunction "2_2") (pintype "passive"))
      (node (ref "C6") (pin "2") (pinfunction "2_2") (pintype "passive"))
      (node (ref "D1") (pin "1") (pinfunction "A_1") (pintype "passive"))
      (node (ref "D3") (pin "2") (pinfunction "K_2") (pintype "passive"))
      (node (ref "P1") (pin "1") (pinfunction "1_1") (pintype "passive"))
      (node (ref "P1") (pin "3") (pinfunction "3_3") (pintype "passive"))
      (node (ref "P10") (pin "42") (pinfunction "GND*_42") (pintype "passive"))
      (node (ref "P11") (pin "14") (pinfunction "AGND_14") (pintype "passive"))
      (node (ref "P11") (pin "19") (pinfunction "GND*_19") (pintype "passive"))
      (node (ref "P11") (pin "20") (pinfunction "GND*_20") (pintype "passive"))
      (node (ref "P14") (pin "3") (pinfunction "3_3") (pintype "passive"))
      (node (ref "P15") (pin "3") (pinfunction "3_3") (pintype "passive"))
      (node (ref "P2") (pin "1") (pinfunction "1_1") (pintype "passive"))
      (node (ref "P20") (pin "3") (pinfunction "3_3") (pintype "passive"))
      (node (ref "P21") (pin "3") (pinfunction "3_3") (pintype "passive"))
      (node (ref "P6") (pin "1") (pinfunction "1_1") (pintype "passive"))
      (node (ref "P6") (pin "3") (pinfunction "3_3") (pintype "passive"))
      (node (ref "P7") (pin "1") (pinfunction "1_1") (pintype "passive"))
      (node (ref "P7") (pin "3") (pinfunction "3_3") (pintype "passive"))
      (node (ref "P9") (pin "1") (pinfunction "1_1") (pintype "passive"))
      (node (ref "R1") (pin "2") (pinfunction "2_2") (pintype "passive"))
      (node (ref "R12") (pin "2") (pinfunction "2_2") (pintype "passive"))
      (node (ref "R13") (pin "1") (pinfunction "1_1") (pintype "passive"))
      (node (ref "R2") (pin "1") (pinfunction "1_1") (pintype "passive"))
      (node (ref "R28") (pin "1") (pinfunction "1_1") (pintype "passive"))
      (node (ref "R3") (pin "2") (pinfunction "2_2") (pintype "passive"))
      (node (ref "R4") (pin "1") (pinfunction "1_1") (pintype "passive"))
      (node (ref "R5") (pin "2") (pinfunction "2_2") (pintype "passive"))
      (node (ref "R6") (pin "1") (pinfunction "1_1") (pintype "passive"))
      (node (ref "U1") (pin "14") (pinfunction "GND_14") (pintype "passive"))
      (node (ref "U1") (pin "28") (pinfunction "GND_28") (pintype "passive"))
      (node (ref "U1") (pin "29") (pinfunction "GND_29") (pintype "passive"))
      (node (ref "U2") (pin "14") (pinfunction "GND_14") (pintype "passive"))
      (node (ref "U2") (pin "28") (pinfunction "GND_28") (pintype "passive"))
      (node (ref "U2") (pin "29") (pinfunction "GND_29") (pintype "passive"))
      (node (ref "U3") (pin "14") (pinfunction "GND_14") (pintype "passive"))
      (node (ref "U3") (pin "28") (pinfunction "GND_28") (pintype "passive"))
      (node (ref "U3") (pin "29") (pinfunction "GND_29") (pintype "passive"))
      (node (ref "U4") (pin "14") (pinfunction "GND_14") (pintype "passive"))
      (node (ref "U4") (pin "28") (pinfunction "GND_28") (pintype "passive"))
      (node (ref "U4") (pin "29") (pinfunction "GND_29") (pintype "passive"))
      (node (ref "U5") (pin "1") (pinfunction "GND_1") (pintype "passive"))
      (node (ref "U6") (pin "13") (pinfunction "P0B_13") (pintype "passive"))
      (node (ref "U6") (pin "16") (pinfunction "A1_16") (pintype "passive"))
      (node (ref "U6") (pin "18") (pinfunction "P2B_18") (pintype "passive"))
      (node (ref "U6") (pin "3") (pinfunction "P3B_3") (pintype "passive"))
      (node (ref "U6") (pin "4") (pinfunction "HVC/A0_4") (pintype "passive"))
      (node (ref "U6") (pin "7") (pinfunction "VSS_7") (pintype "passive"))
      (node (ref "U6") (pin "8") (pinfunction "P1B_8") (pintype "passive"))
      (node (ref "U7") (pin "7") (pinfunction "GND_7") (pintype "passive"))
      (node (ref "U8") (pin "2") (pinfunction "GND_2") (pintype "passive"))
      (node (ref "U9") (pin "7") (pinfunction "GND_7") (pintype "passive"))
    )
    (net (code "64") (name "Net-(C25-Pad1)") (class "Default")
      (node (ref "C25") (pin "1") (pinfunction "1_1") (pintype "passive"))
      (node (ref "R26") (pin "1") (pinfunction "1_1") (pintype "passive"))
      (node (ref "R27") (pin "2") (pinfunction "2_2") (pintype "passive"))
    )
    (net (code "65") (name "Net-(D2-K)") (class "Default")
      (node (ref "D2") (pin "2") (pinfunction "K_2") (pintype "passive"))
      (node (ref "R17") (pin "2") (pinfunction "2_2") (pintype "passive"))
    )
    (net (code "66") (name "Net-(D3-A)") (class "Default")
      (node (ref "D3") (pin "1") (pinfunction "A_1") (pintype "passive"))
      (node (ref "R14") (pin "2") (pinfunction "2_2") (pintype "passive"))
    )
    (net (code "67") (name "Net-(D4-K)") (class "Default")
      (node (ref "D4") (pin "2") (pinfunction "K_2") (pintype "passive"))
      (node (ref "R19") (pin "2") (pinfunction "2_2") (pintype "passive"))
    )
    (net (code "68") (name "Net-(D5-K)") (class "Default")
      (node (ref "D5") (pin "2") (pinfunction "K_2") (pintype "passive"))
      (node (ref "R25") (pin "2") (pinfunction "2_2") (pintype "passive"))
    )
    (net (code "69") (name "Net-(D6-K)") (class "Default")
      (node (ref "D6") (pin "2") (pinfunction "K_2") (pintype "passive"))
      (node (ref "R29") (pin "2") (pinfunction "2_2") (pintype "passive"))
    )
    (net (code "70") (name "Net-(F1-Pad1)") (class "Default")
      (node (ref "F1") (pin "1") (pinfunction "1_1") (pintype "passive"))
      (node (ref "P2") (pin "2") (pinfunction "2_2") (pintype "passive"))
    )
    (net (code "71") (name "Net-(U1-CP1)") (class "Default")
      (node (ref "C1") (pin "2") (pinfunction "2_2") (pintype "passive"))
      (node (ref "U1") (pin "1") (pinfunction "CP1_1") (pintype "passive"))
    )
    (net (code "72") (name "Net-(U1-CP2)") (class "Default")
      (node (ref "C1") (pin "1") (pinfunction "1_1") (pintype "passive"))
      (node (ref "U1") (pin "2") (pinfunction "CP2_2") (pintype "passive"))
    )
    (net (code "73") (name "Net-(U1-DECAY)") (class "Default")
      (node (ref "P14") (pin "1") (pintype "passive"))
      (node (ref "U1") (pin "19") (pinfunction "DECAY_19") (pintype "passive"))
    )
    (net (code "74") (name "Net-(U1-MODE0)") (class "Default")
      (node (ref "P16") (pin "6") (pinfunction "6_6") (pintype "passive"))
      (node (ref "U1") (pin "24") (pinfunction "MODE0_24") (pintype "passive"))
    )
    (net (code "75") (name "Net-(U1-MODE1)") (class "Default")
      (node (ref "P16") (pin "5") (pinfunction "5_5") (pintype "passive"))
      (node (ref "U1") (pin "25") (pinfunction "MODE1_25") (pintype "passive"))
    )
    (net (code "76") (name "Net-(U1-MODE2)") (class "Default")
      (node (ref "P16") (pin "4") (pinfunction "4_4") (pintype "passive"))
      (node (ref "U1") (pin "26") (pinfunction "MODE2_26") (pintype "passive"))
    )
    (net (code "77") (name "Net-(U1-VCP)") (class "Default")
      (node (ref "C7") (pin "1") (pinfunction "1_1") (pintype "passive"))
      (node (ref "U1") (pin "3") (pinfunction "VCP_3") (pintype "passive"))
    )
    (net (code "78") (name "Net-(U2-CP1)") (class "Default")
      (node (ref "C2") (pin "2") (pinfunction "2_2") (pintype "passive"))
      (node (ref "U2") (pin "1") (pinfunction "CP1_1") (pintype "passive"))
    )
    (net (code "79") (name "Net-(U2-CP2)") (class "Default")
      (node (ref "C2") (pin "1") (pinfunction "1_1") (pintype "passive"))
      (node (ref "U2") (pin "2") (pinfunction "CP2_2") (pintype "passive"))
    )
    (net (code "80") (name "Net-(U2-DECAY)") (class "Default")
      (node (ref "P15") (pin "1") (pintype "passive"))
      (node (ref "U2") (pin "19") (pinfunction "DECAY_19") (pintype "passive"))
    )
    (net (code "81") (name "Net-(U2-MODE0)") (class "Default")
      (node (ref "P17") (pin "6") (pinfunction "6_6") (pintype "passive"))
      (node (ref "U2") (pin "24") (pinfunction "MODE0_24") (pintype "passive"))
    )
    (net (code "82") (name "Net-(U2-MODE1)") (class "Default")
      (node (ref "P17") (pin "5") (pinfunction "5_5") (pintype "passive"))
      (node (ref "U2") (pin "25") (pinfunction "MODE1_25") (pintype "passive"))
    )
    (net (code "83") (name "Net-(U2-MODE2)") (class "Default")
      (node (ref "P17") (pin "4") (pinfunction "4_4") (pintype "passive"))
      (node (ref "U2") (pin "26") (pinfunction "MODE2_26") (pintype "passive"))
    )
    (net (code "84") (name "Net-(U2-VCP)") (class "Default")
      (node (ref "C10") (pin "1") (pinfunction "1_1") (pintype "passive"))
      (node (ref "U2") (pin "3") (pinfunction "VCP_3") (pintype "passive"))
    )
    (net (code "85") (name "Net-(U3-CP1)") (class "Default")
      (node (ref "C3") (pin "2") (pinfunction "2_2") (pintype "passive"))
      (node (ref "U3") (pin "1") (pinfunction "CP1_1") (pintype "passive"))
    )
    (net (code "86") (name "Net-(U3-CP2)") (class "Default")
      (node (ref "C3") (pin "1") (pinfunction "1_1") (pintype "passive"))
      (node (ref "U3") (pin "2") (pinfunction "CP2_2") (pintype "passive"))
    )
    (net (code "87") (name "Net-(U3-DECAY)") (class "Default")
      (node (ref "P20") (pin "1") (pintype "passive"))
      (node (ref "U3") (pin "19") (pinfunction "DECAY_19") (pintype "passive"))
    )
    (net (code "88") (name "Net-(U3-MODE0)") (class "Default")
      (node (ref "P18") (pin "6") (pinfunction "6_6") (pintype "passive"))
      (node (ref "U3") (pin "24") (pinfunction "MODE0_24") (pintype "passive"))
    )
    (net (code "89") (name "Net-(U3-MODE1)") (class "Default")
      (node (ref "P18") (pin "5") (pinfunction "5_5") (pintype "passive"))
      (node (ref "U3") (pin "25") (pinfunction "MODE1_25") (pintype "passive"))
    )
    (net (code "90") (name "Net-(U3-MODE2)") (class "Default")
      (node (ref "P18") (pin "4") (pinfunction "4_4") (pintype "passive"))
      (node (ref "U3") (pin "26") (pinfunction "MODE2_26") (pintype "passive"))
    )
    (net (code "91") (name "Net-(U3-VCP)") (class "Default")
      (node (ref "C13") (pin "1") (pinfunction "1_1") (pintype "passive"))
      (node (ref "U3") (pin "3") (pinfunction "VCP_3") (pintype "passive"))
    )
    (net (code "92") (name "Net-(U4-CP1)") (class "Default")
      (node (ref "C19") (pin "2") (pinfunction "2_2") (pintype "passive"))
      (node (ref "U4") (pin "1") (pinfunction "CP1_1") (pintype "passive"))
    )
    (net (code "93") (name "Net-(U4-CP2)") (class "Default")
      (node (ref "C19") (pin "1") (pinfunction "1_1") (pintype "passive"))
      (node (ref "U4") (pin "2") (pinfunction "CP2_2") (pintype "passive"))
    )
    (net (code "94") (name "Net-(U4-DECAY)") (class "Default")
      (node (ref "P21") (pin "1") (pintype "passive"))
      (node (ref "U4") (pin "19") (pinfunction "DECAY_19") (pintype "passive"))
    )
    (net (code "95") (name "Net-(U4-MODE0)") (class "Default")
      (node (ref "P19") (pin "6") (pinfunction "6_6") (pintype "passive"))
      (node (ref "U4") (pin "24") (pinfunction "MODE0_24") (pintype "passive"))
    )
    (net (code "96") (name "Net-(U4-MODE1)") (class "Default")
      (node (ref "P19") (pin "5") (pinfunction "5_5") (pintype "passive"))
      (node (ref "U4") (pin "25") (pinfunction "MODE1_25") (pintype "passive"))
    )
    (net (code "97") (name "Net-(U4-MODE2)") (class "Default")
      (node (ref "P19") (pin "4") (pinfunction "4_4") (pintype "passive"))
      (node (ref "U4") (pin "26") (pinfunction "MODE2_26") (pintype "passive"))
    )
    (net (code "98") (name "Net-(U4-VCP)") (class "Default")
      (node (ref "C23") (pin "1") (pinfunction "1_1") (pintype "passive"))
      (node (ref "U4") (pin "3") (pinfunction "VCP_3") (pintype "passive"))
    )
    (net (code "99") (name "Net-(U6-P0A)") (class "Default")
      (node (ref "R8") (pin "1") (pinfunction "1_1") (pintype "passive"))
      (node (ref "U6") (pin "1") (pinfunction "P3A_1") (pintype "passive"))
      (node (ref "U6") (pin "10") (pinfunction "P1A_10") (pintype "passive"))
      (node (ref "U6") (pin "11") (pinfunction "P0A_11") (pintype "passive"))
      (node (ref "U6") (pin "20") (pinfunction "P2A_20") (pintype "passive"))
    )
    (net (code "100") (name "Net-(U6-nRESET)") (class "Default")
      (node (ref "R9") (pin "1") (pinfunction "1_1") (pintype "passive"))
      (node (ref "U6") (pin "15") (pinfunction "nRESET_15") (pintype "passive"))
    )
    (net (code "101") (name "Net-(U7-1Y)") (class "Default")
      (node (ref "U7") (pin "3") (pinfunction "1Y_3") (pintype "passive"))
      (node (ref "U7") (pin "4") (pinfunction "2A_4") (pintype "passive"))
    )
    (net (code "102") (name "Net-(U7-2B)") (class "Default")
      (node (ref "R21") (pin "1") (pinfunction "1_1") (pintype "passive"))
      (node (ref "U7") (pin "5") (pinfunction "2B_5") (pintype "passive"))
    )
    (net (code "103") (name "Net-(U7-3Y)") (class "Default")
      (node (ref "U7") (pin "12") (pinfunction "4A_12") (pintype "passive"))
      (node (ref "U7") (pin "8") (pinfunction "3Y_8") (pintype "passive"))
    )
    (net (code "104") (name "Net-(U7-4B)") (class "Default")
      (node (ref "R23") (pin "1") (pinfunction "1_1") (pintype "passive"))
      (node (ref "U7") (pin "13") (pinfunction "4B_13") (pintype "passive"))
    )
    (net (code "105") (name "Net-(U9-1Y)") (class "Default")
      (node (ref "U9") (pin "3") (pinfunction "1Y_3") (pintype "passive"))
      (node (ref "U9") (pin "4") (pinfunction "2A_4") (pintype "passive"))
    )
    (net (code "106") (name "Net-(U9-2B)") (class "Default")
      (node (ref "R31") (pin "1") (pinfunction "1_1") (pintype "passive"))
      (node (ref "U9") (pin "5") (pinfunction "2B_5") (pintype "passive"))
    )
    (net (code "107") (name "Net-(U9-3Y)") (class "Default")
      (node (ref "U9") (pin "12") (pinfunction "4A_12") (pintype "passive"))
      (node (ref "U9") (pin "8") (pinfunction "3Y_8") (pintype "passive"))
    )
    (net (code "108") (name "Net-(U9-4B)") (class "Default")
      (node (ref "R30") (pin "1") (pinfunction "1_1") (pintype "passive"))
      (node (ref "U9") (pin "13") (pinfunction "4B_13") (pintype "passive"))
    )
    (net (code "109") (name "VM") (class "Default")
      (node (ref "C10") (pin "2") (pinfunction "2_2") (pintype "passive"))
      (node (ref "C12") (pin "2") (pinfunction "2_2") (pintype "passive"))
      (node (ref "C13") (pin "2") (pinfunction "2_2") (pintype "passive"))
      (node (ref "C15") (pin "1") (pinfunction "1_1") (pintype "passive"))
      (node (ref "C21") (pin "1") (pinfunction "1_1") (pintype "passive"))
      (node (ref "C23") (pin "2") (pinfunction "2_2") (pintype "passive"))
      (node (ref "C4") (pin "1") (pinfunction "1_1") (pintype "passive"))
      (node (ref "C5") (pin "1") (pinfunction "1_1") (pintype "passive"))
      (node (ref "C6") (pin "1") (pinfunction "1_1") (pintype "passive"))
      (node (ref "C7") (pin "2") (pinfunction "2_2") (pintype "passive"))
      (node (ref "D1") (pin "2") (pinfunction "K_2") (pintype "passive"))
      (node (ref "F1") (pin "2") (pinfunction "2_2") (pintype "passive"))
      (node (ref "P6") (pin "2") (pinfunction "2_2") (pintype "passive"))
      (node (ref "R15") (pin "2") (pinfunction "2_2") (pintype "passive"))
      (node (ref "U1") (pin "11") (pinfunction "VMB_11") (pintype "passive"))
      (node (ref "U1") (pin "4") (pinfunction "VMA_4") (pintype "passive"))
      (node (ref "U2") (pin "11") (pinfunction "VMB_11") (pintype "passive"))
      (node (ref "U2") (pin "4") (pinfunction "VMA_4") (pintype "passive"))
      (node (ref "U3") (pin "11") (pinfunction "VMB_11") (pintype "passive"))
      (node (ref "U3") (pin "4") (pinfunction "VMA_4") (pintype "passive"))
      (node (ref "U4") (pin "11") (pinfunction "VMB_11") (pintype "passive"))
      (node (ref "U4") (pin "4") (pinfunction "VMA_4") (pintype "passive"))
      (node (ref "U5") (pin "3") (pinfunction "Vin_3") (pintype "passive"))
    )
    (net (code "110") (name "unconnected-(P10-DIR4-Pad28)") (class "Default")
      (node (ref "P10") (pin "28") (pinfunction "DIR4_28") (pintype "passive"))
    )
    (net (code "111") (name "unconnected-(P10-DIR5-Pad44)") (class "Default")
      (node (ref "P10") (pin "44") (pinfunction "DIR5_44") (pintype "passive"))
    )
    (net (code "112") (name "unconnected-(P10-EN*-Pad36)") (class "Default")
      (node (ref "P10") (pin "36") (pinfunction "EN*_36") (pintype "passive"))
    )
    (net (code "113") (name "unconnected-(P10-P2.6-Pad52)") (class "Default")
      (node (ref "P10") (pin "52") (pinfunction "P2.6_52") (pintype "passive"))
    )
    (net (code "114") (name "unconnected-(P10-P2.7-Pad51)") (class "Default")
      (node (ref "P10") (pin "51") (pinfunction "P2.7_51") (pintype "passive"))
    )
    (net (code "115") (name "unconnected-(P10-PLAY-Pad45)") (class "Default")
      (node (ref "P10") (pin "45") (pinfunction "PLAY_45") (pintype "passive"))
    )
    (net (code "116") (name "unconnected-(P10-SD_CD-Pad46)") (class "Default")
      (node (ref "P10") (pin "46") (pinfunction "SD_CD_46") (pintype "passive"))
    )
    (net (code "117") (name "unconnected-(P10-STP4-Pad29)") (class "Default")
      (node (ref "P10") (pin "29") (pinfunction "STP4_29") (pintype "passive"))
    )
    (net (code "118") (name "unconnected-(P10-STP_5-Pad47)") (class "Default")
      (node (ref "P10") (pin "47") (pinfunction "STP_5_47") (pintype "passive"))
    )
    (net (code "119") (name "unconnected-(P11-AVCC-Pad13)") (class "Default")
      (node (ref "P11") (pin "13") (pinfunction "AVCC_13") (pintype "passive"))
    )
    (net (code "120") (name "unconnected-(P11-EN4-Pad21)") (class "Default")
      (node (ref "P11") (pin "21") (pinfunction "EN4_21") (pintype "passive"))
    )
    (net (code "121") (name "unconnected-(P11-EN_5-Pad1)") (class "Default")
      (node (ref "P11") (pin "1") (pinfunction "EN_5_1") (pintype "passive"))
    )
    (net (code "122") (name "unconnected-(P11-MISO1-Pad6)") (class "Default")
      (node (ref "P11") (pin "6") (pinfunction "MISO1_6") (pintype "passive"))
    )
    (net (code "123") (name "unconnected-(P11-MOSI1-Pad5)") (class "Default")
      (node (ref "P11") (pin "5") (pinfunction "MOSI1_5") (pintype "passive"))
    )
    (net (code "124") (name "unconnected-(P11-P1.22-Pad9)") (class "Default")
      (node (ref "P11") (pin "9") (pinfunction "P1.22_9") (pintype "passive"))
    )
    (net (code "125") (name "unconnected-(P11-P1.23-Pad10)") (class "Default")
      (node (ref "P11") (pin "10") (pinfunction "P1.23_10") (pintype "passive"))
    )
    (net (code "126") (name "unconnected-(P11-P1.30-Pad11)") (class "Default")
      (node (ref "P11") (pin "11") (pinfunction "P1.30_11") (pintype "passive"))
    )
    (net (code "127") (name "unconnected-(P11-P1.31-Pad12)") (class "Default")
      (node (ref "P11") (pin "12") (pinfunction "P1.31_12") (pintype "passive"))
    )
    (net (code "128") (name "unconnected-(P11-PLAY_LED-Pad2)") (class "Default")
      (node (ref "P11") (pin "2") (pinfunction "PLAY_LED_2") (pintype "passive"))
    )
    (net (code "129") (name "unconnected-(P11-SCK1-Pad8)") (class "Default")
      (node (ref "P11") (pin "8") (pinfunction "SCK1_8") (pintype "passive"))
    )
    (net (code "130") (name "unconnected-(P11-SD_IRQ-Pad4)") (class "Default")
      (node (ref "P11") (pin "4") (pinfunction "SD_IRQ_4") (pintype "passive"))
    )
    (net (code "131") (name "unconnected-(P11-SD_WP-Pad3)") (class "Default")
      (node (ref "P11") (pin "3") (pinfunction "SD_WP_3") (pintype "passive"))
    )
    (net (code "132") (name "unconnected-(P11-SSEL1-Pad7)") (class "Default")
      (node (ref "P11") (pin "7") (pinfunction "SSEL1_7") (pintype "passive"))
    )
    (net (code "133") (name "unconnected-(P11-TH1-Pad27)") (class "Default")
      (node (ref "P11") (pin "27") (pinfunction "TH1_27") (pintype "passive"))
    )
    (net (code "134") (name "unconnected-(P11-TH2-Pad26)") (class "Default")
      (node (ref "P11") (pin "26") (pinfunction "TH2_26") (pintype "passive"))
    )
    (net (code "135") (name "unconnected-(P11-TH3-Pad25)") (class "Default")
      (node (ref "P11") (pin "25") (pinfunction "TH3_25") (pintype "passive"))
    )
    (net (code "136") (name "unconnected-(P11-TH4-Pad24)") (class "Default")
      (node (ref "P11") (pin "24") (pinfunction "TH4_24") (pintype "passive"))
    )
    (net (code "137") (name "unconnected-(U1-nHOME-Pad27)") (class "Default")
      (node (ref "U1") (pin "27") (pinfunction "nHOME_27") (pintype "passive+no_connect"))
    )
    (net (code "138") (name "unconnected-(U2-nHOME-Pad27)") (class "Default")
      (node (ref "U2") (pin "27") (pinfunction "nHOME_27") (pintype "passive+no_connect"))
    )
    (net (code "139") (name "unconnected-(U3-nHOME-Pad27)") (class "Default")
      (node (ref "U3") (pin "27") (pinfunction "nHOME_27") (pintype "passive+no_connect"))
    )
    (net (code "140") (name "unconnected-(U4-nHOME-Pad27)") (class "Default")
      (node (ref "U4") (pin "27") (pinfunction "nHOME_27") (pintype "passive+no_connect"))
    )
    (net (code "141") (name "unconnected-(U6-NC-Pad14)") (class "Default")
      (node (ref "U6") (pin "14") (pinfunction "NC_14") (pintype "passive"))
    )
  )
)
